# Total.net
KiCad netlist of a schematic drawn in Altium Designer
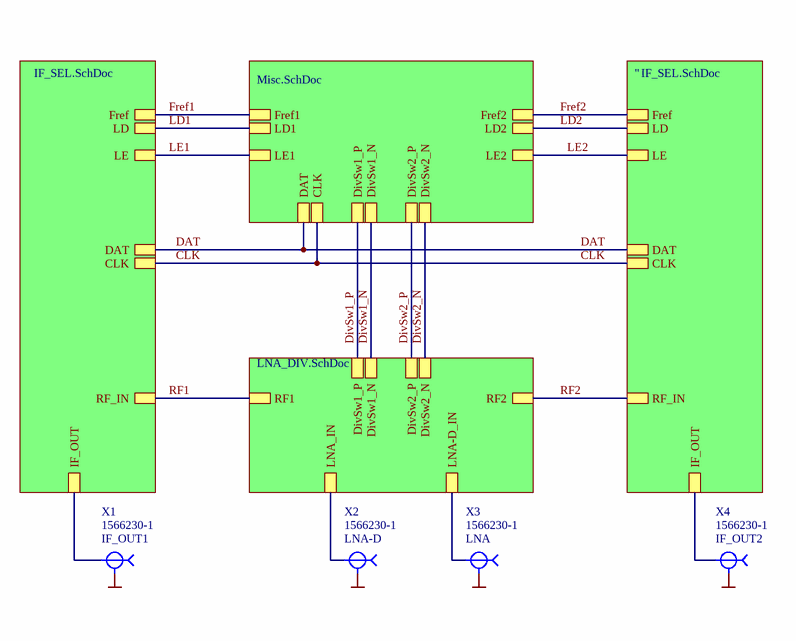
[diagram p0: Total.SCHDOC]

(export (version "E")
  (design (tool "Eeschema 10.0.6"))
  (components
    (comp (ref "X1")
      (value "1566230-1")
      (footprint "U_FL")
      (description "Connector (UMCC)")
      (fields (field (name "MANUFACTURER") "Tyco Electronics Corp") (field (name "DSCRIPTION") "IF_OUT1"))
      (libsource (lib "Andy") (part "U_FL"))
    )
    (comp (ref "X2")
      (value "1566230-1")
      (footprint "U_FL")
      (description "Connector (UMCC)")
      (fields (field (name "MANUFACTURER") "Tyco Electronics Corp") (field (name "DSCRIPTION") "LNA-D"))
      (libsource (lib "Andy") (part "U_FL"))
    )
    (comp (ref "X3")
      (value "1566230-1")
      (footprint "U_FL")
      (description "Connector (UMCC)")
      (fields (field (name "MANUFACTURER") "Tyco Electronics Corp") (field (name "DSCRIPTION") "LNA"))
      (libsource (lib "Andy") (part "U_FL"))
    )
    (comp (ref "X4")
      (value "1566230-1")
      (footprint "U_FL")
      (description "Connector (UMCC)")
      (fields (field (name "MANUFACTURER") "Tyco Electronics Corp") (field (name "DSCRIPTION") "IF_OUT2"))
      (libsource (lib "Andy") (part "U_FL"))
    )
  )
  (nets
    (net (code "9") (name "/IF_OUT") (class "Default")
      (node (ref "X4") (pin "1") (pinfunction "1_1") (pintype "passive"))
    )
    (net (code "10") (name "/IF_OUT_1") (class "Default")
      (node (ref "X1") (pin "1") (pinfunction "1_1") (pintype "passive"))
    )
    (net (code "15") (name "/LNA-D_IN") (class "Default")
      (node (ref "X3") (pin "1") (pinfunction "1_1") (pintype "passive"))
    )
    (net (code "16") (name "/LNA_IN") (class "Default")
      (node (ref "X2") (pin "1") (pinfunction "1_1") (pintype "passive"))
    )
    (net (code "19") (name "GND") (class "Default")
      (node (ref "X1") (pin "2") (pinfunction "GND_2") (pintype "passive"))
      (node (ref "X2") (pin "2") (pinfunction "GND_2") (pintype "passive"))
      (node (ref "X3") (pin "2") (pinfunction "GND_2") (pintype "passive"))
      (node (ref "X4") (pin "2") (pinfunction "GND_2") (pintype "passive"))
    )
  )
)
